# SCH_FB-Collar-Module_2024-04-16.net
KiCad netlist of a schematic drawn in EasyEDA
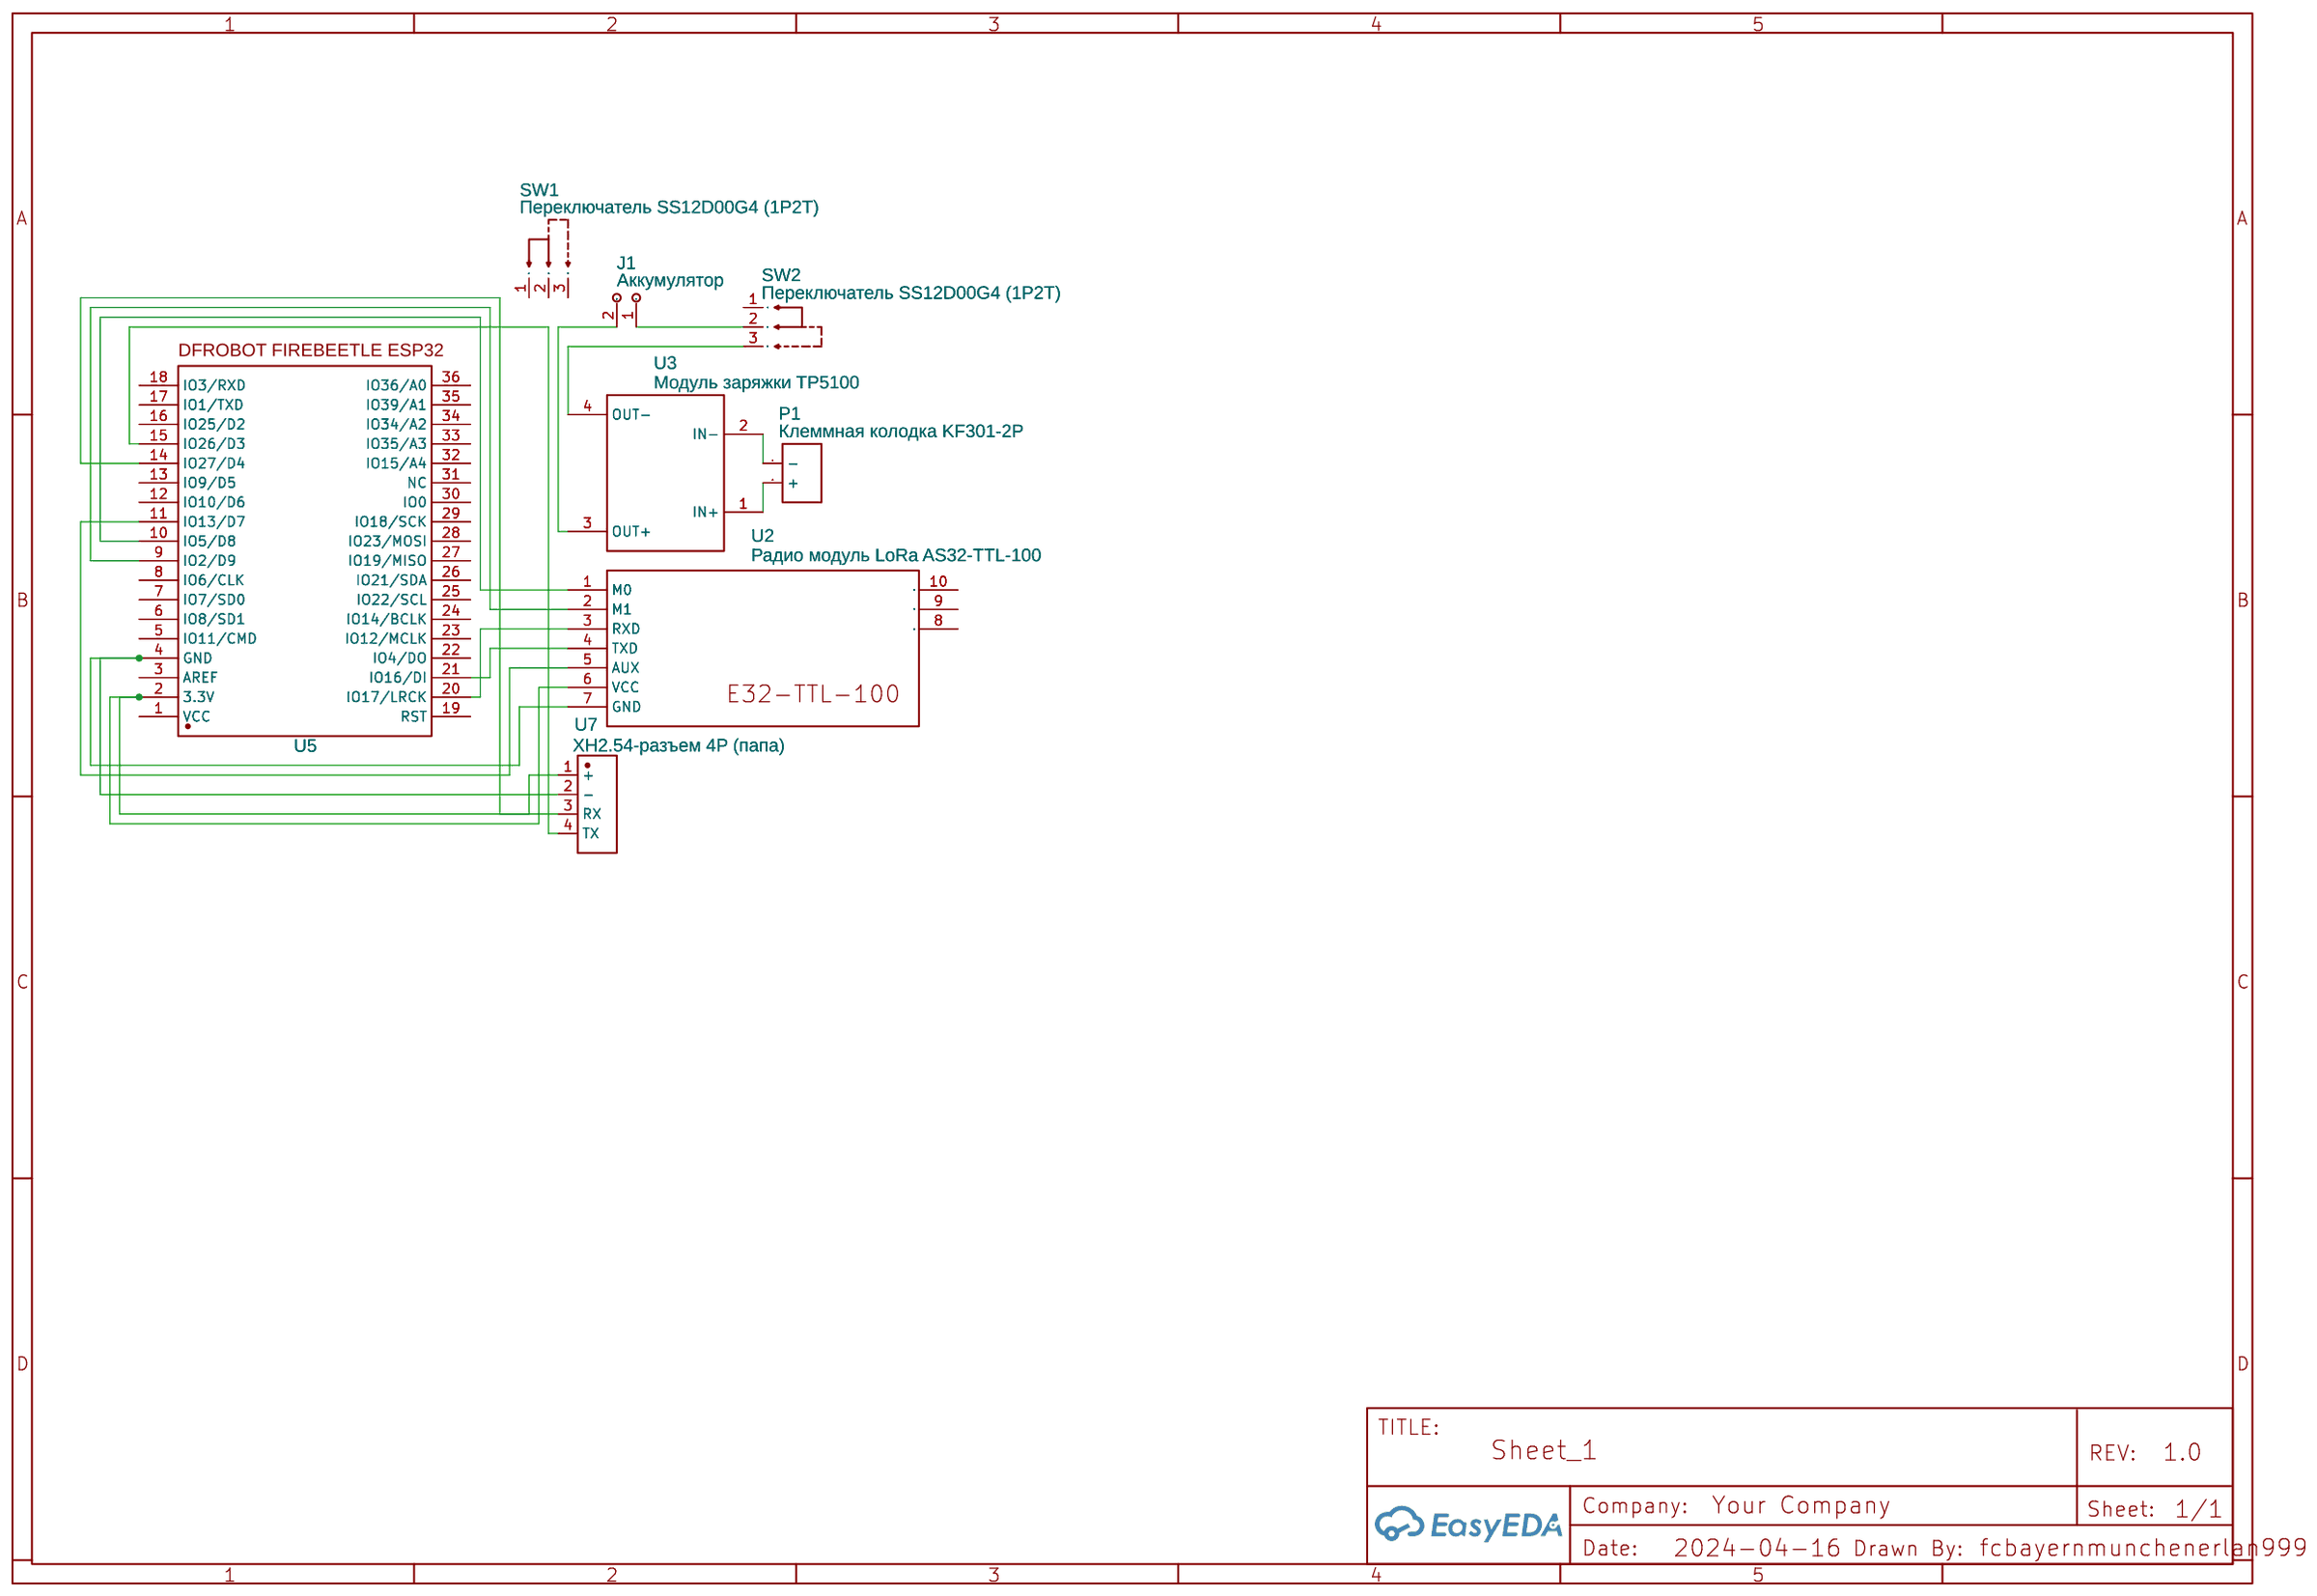
[diagram p0: schematic sheet]

(export (version "E")
  (design (tool "Eeschema 10.0.6"))
  (components
    (comp (ref "J1") (value "Аккумулятор") (libsource (lib "") (part "2xhole")))
    (comp (ref "P1") (value "Клеммная колодка KF301-2P") (libsource (lib "") (part "CONN-TH_2P-P5.00")))
    (comp (ref "SW1")
      (value "Переключатель SS12D00G4 (1P2T)")
      (fields (field (name "Manufacturer Part") "SS-12E17-G020") (field (name "Manufacturer") "G-Switch(品赞)"))
      (libsource (lib "") (part "SS-12E17-G020"))
    )
    (comp (ref "SW2")
      (value "Переключатель SS12D00G4 (1P2T)")
      (fields (field (name "Manufacturer Part") "SS-12E17-G020") (field (name "Manufacturer") "G-Switch(品赞)"))
      (libsource (lib "") (part "SS-12E17-G020_1"))
    )
    (comp (ref "U2")
      (value "Радио модуль LoRa AS32-TTL-100")
      (fields (field (name "Manufacturer Part") "E32-433T20DC") (field (name "Manufacturer") "EBYTE(亿佰特)"))
      (libsource (lib "") (part "E32-TTL-100"))
    )
    (comp (ref "U3") (value "Модуль заряжки TP5100") (libsource (lib "") (part "TP5100_MODULE_CHARGER")))
    (comp (ref "U5") (value "DFROBOT_FIREBEETLE") (libsource (lib "") (part "DFROBOT_FIREBEETLE")))
    (comp (ref "U7")
      (value "XH2.54-разъем 4P (папа)")
      (fields
        (field (name "Manufacturer Part") "ZX-XH2.54-4PWZ")
        (field (name "Manufacturer") "Megastar(兆星)")
      )
      (libsource (lib "") (part "ZX-XH2.54-4PWZ"))
    )
  )
  (nets
    (net (code "1") (name "Net-(J1-Pad1)") (class "Default")
      (node (ref "J1") (pin "1") (pinfunction "1_1") (pintype "unspecified"))
      (node (ref "SW2") (pin "2") (pinfunction "2_2") (pintype "unspecified"))
    )
    (net (code "2") (name "Net-(P1-+)") (class "Default")
      (node (ref "P1") (pin "2") (pinfunction "+_2") (pintype "unspecified"))
      (node (ref "U3") (pin "1") (pinfunction "IN+_1") (pintype "unspecified"))
    )
    (net (code "3") (name "Net-(P1--)") (class "Default")
      (node (ref "P1") (pin "1") (pinfunction "-_1") (pintype "unspecified"))
      (node (ref "U3") (pin "2") (pinfunction "IN-_2") (pintype "unspecified"))
    )
    (net (code "4") (name "Net-(U2-AUX)") (class "Default")
      (node (ref "U2") (pin "5") (pinfunction "AUX_5") (pintype "unspecified"))
      (node (ref "U5") (pin "11") (pinfunction "IO13/D7_11") (pintype "unspecified"))
    )
    (net (code "5") (name "Net-(U2-GND)") (class "Default")
      (node (ref "U2") (pin "7") (pinfunction "GND_7") (pintype "unspecified"))
      (node (ref "U5") (pin "4") (pinfunction "GND_4") (pintype "unspecified"))
      (node (ref "U7") (pin "2") (pinfunction "-_2") (pintype "unspecified"))
    )
    (net (code "6") (name "Net-(U2-M0)") (class "Default")
      (node (ref "U2") (pin "1") (pinfunction "M0_1") (pintype "unspecified"))
      (node (ref "U5") (pin "10") (pinfunction "IO5/D8_10") (pintype "unspecified"))
    )
    (net (code "7") (name "Net-(U2-M1)") (class "Default")
      (node (ref "U2") (pin "2") (pinfunction "M1_2") (pintype "unspecified"))
      (node (ref "U5") (pin "9") (pinfunction "IO2/D9_9") (pintype "unspecified"))
    )
    (net (code "8") (name "Net-(U2-RXD)") (class "Default")
      (node (ref "U2") (pin "3") (pinfunction "RXD_3") (pintype "unspecified"))
      (node (ref "U5") (pin "20") (pinfunction "IO17/LRCK_20") (pintype "unspecified"))
    )
    (net (code "9") (name "Net-(U2-TXD)") (class "Default")
      (node (ref "U2") (pin "4") (pinfunction "TXD_4") (pintype "unspecified"))
      (node (ref "U5") (pin "21") (pinfunction "IO16/DI_21") (pintype "unspecified"))
    )
    (net (code "10") (name "Net-(U2-VCC)") (class "Default")
      (node (ref "U2") (pin "6") (pinfunction "VCC_6") (pintype "passive"))
      (node (ref "U5") (pin "2") (pinfunction "3.3V_2") (pintype "unspecified"))
      (node (ref "U7") (pin "1") (pinfunction "+_1") (pintype "unspecified"))
    )
    (net (code "11") (name "Net-(U3-OUT+)") (class "Default")
      (node (ref "J1") (pin "2") (pinfunction "2_2") (pintype "unspecified"))
      (node (ref "U3") (pin "3") (pinfunction "OUT+_3") (pintype "unspecified"))
    )
    (net (code "12") (name "Net-(U3-OUT-)") (class "Default")
      (node (ref "SW2") (pin "3") (pinfunction "3_3") (pintype "unspecified"))
      (node (ref "U3") (pin "4") (pinfunction "OUT-_4") (pintype "unspecified"))
    )
    (net (code "13") (name "Net-(U5-IO26{slash}D3)") (class "Default")
      (node (ref "U5") (pin "15") (pinfunction "IO26/D3_15") (pintype "unspecified"))
      (node (ref "U7") (pin "4") (pinfunction "TX_4") (pintype "unspecified"))
    )
    (net (code "14") (name "Net-(U5-IO27{slash}D4)") (class "Default")
      (node (ref "U5") (pin "14") (pinfunction "IO27/D4_14") (pintype "unspecified"))
      (node (ref "U7") (pin "3") (pinfunction "RX_3") (pintype "unspecified"))
    )
    (net (code "15") (name "unconnected-(SW1-Pad1)") (class "Default")
      (node (ref "SW1") (pin "1") (pinfunction "1_1") (pintype "unspecified"))
    )
    (net (code "16") (name "unconnected-(SW1-Pad2)") (class "Default")
      (node (ref "SW1") (pin "2") (pinfunction "2_2") (pintype "unspecified"))
    )
    (net (code "17") (name "unconnected-(SW1-Pad3)") (class "Default")
      (node (ref "SW1") (pin "3") (pinfunction "3_3") (pintype "unspecified"))
    )
    (net (code "18") (name "unconnected-(SW2-Pad1)") (class "Default")
      (node (ref "SW2") (pin "1") (pinfunction "1_1") (pintype "unspecified"))
    )
    (net (code "19") (name "unconnected-(U2-Pad8)") (class "Default")
      (node (ref "U2") (pin "8") (pinfunction "8_8") (pintype "unspecified"))
    )
    (net (code "20") (name "unconnected-(U2-Pad9)") (class "Default")
      (node (ref "U2") (pin "9") (pinfunction "9_9") (pintype "unspecified"))
    )
    (net (code "21") (name "unconnected-(U2-Pad10)") (class "Default")
      (node (ref "U2") (pin "10") (pinfunction "10_10") (pintype "unspecified"))
    )
    (net (code "22") (name "unconnected-(U5-AREF-Pad3)") (class "Default")
      (node (ref "U5") (pin "3") (pinfunction "AREF_3") (pintype "unspecified"))
    )
    (net (code "23") (name "unconnected-(U5-IO0-Pad30)") (class "Default")
      (node (ref "U5") (pin "30") (pinfunction "IO0_30") (pintype "unspecified"))
    )
    (net (code "24") (name "unconnected-(U5-IO1{slash}TXD-Pad17)") (class "Default")
      (node (ref "U5") (pin "17") (pinfunction "IO1/TXD_17") (pintype "unspecified"))
    )
    (net (code "25") (name "unconnected-(U5-IO3{slash}RXD-Pad18)") (class "Default")
      (node (ref "U5") (pin "18") (pinfunction "IO3/RXD_18") (pintype "unspecified"))
    )
    (net (code "26") (name "unconnected-(U5-IO4{slash}DO-Pad22)") (class "Default")
      (node (ref "U5") (pin "22") (pinfunction "IO4/DO_22") (pintype "unspecified"))
    )
    (net (code "27") (name "unconnected-(U5-IO6{slash}CLK-Pad8)") (class "Default")
      (node (ref "U5") (pin "8") (pinfunction "IO6/CLK_8") (pintype "unspecified"))
    )
    (net (code "28") (name "unconnected-(U5-IO7{slash}SD0-Pad7)") (class "Default")
      (node (ref "U5") (pin "7") (pinfunction "IO7/SD0_7") (pintype "unspecified"))
    )
    (net (code "29") (name "unconnected-(U5-IO8{slash}SD1-Pad6)") (class "Default")
      (node (ref "U5") (pin "6") (pinfunction "IO8/SD1_6") (pintype "unspecified"))
    )
    (net (code "30") (name "unconnected-(U5-IO9{slash}D5-Pad13)") (class "Default")
      (node (ref "U5") (pin "13") (pinfunction "IO9/D5_13") (pintype "unspecified"))
    )
    (net (code "31") (name "unconnected-(U5-IO10{slash}D6-Pad12)") (class "Default")
      (node (ref "U5") (pin "12") (pinfunction "IO10/D6_12") (pintype "unspecified"))
    )
    (net (code "32") (name "unconnected-(U5-IO11{slash}CMD-Pad5)") (class "Default")
      (node (ref "U5") (pin "5") (pinfunction "IO11/CMD_5") (pintype "unspecified"))
    )
    (net (code "33") (name "unconnected-(U5-IO12{slash}MCLK-Pad23)") (class "Default")
      (node (ref "U5") (pin "23") (pinfunction "IO12/MCLK_23") (pintype "unspecified"))
    )
    (net (code "34") (name "unconnected-(U5-IO14{slash}BCLK-Pad24)") (class "Default")
      (node (ref "U5") (pin "24") (pinfunction "IO14/BCLK_24") (pintype "unspecified"))
    )
    (net (code "35") (name "unconnected-(U5-IO15{slash}A4-Pad32)") (class "Default")
      (node (ref "U5") (pin "32") (pinfunction "IO15/A4_32") (pintype "unspecified"))
    )
    (net (code "36") (name "unconnected-(U5-IO18{slash}SCK-Pad29)") (class "Default")
      (node (ref "U5") (pin "29") (pinfunction "IO18/SCK_29") (pintype "unspecified"))
    )
    (net (code "37") (name "unconnected-(U5-IO19{slash}MISO-Pad27)") (class "Default")
      (node (ref "U5") (pin "27") (pinfunction "IO19/MISO_27") (pintype "unspecified"))
    )
    (net (code "38") (name "unconnected-(U5-IO21{slash}SDA-Pad26)") (class "Default")
      (node (ref "U5") (pin "26") (pinfunction "IO21/SDA_26") (pintype "unspecified"))
    )
    (net (code "39") (name "unconnected-(U5-IO22{slash}SCL-Pad25)") (class "Default")
      (node (ref "U5") (pin "25") (pinfunction "IO22/SCL_25") (pintype "unspecified"))
    )
    (net (code "40") (name "unconnected-(U5-IO23{slash}MOSI-Pad28)") (class "Default")
      (node (ref "U5") (pin "28") (pinfunction "IO23/MOSI_28") (pintype "unspecified"))
    )
    (net (code "41") (name "unconnected-(U5-IO25{slash}D2-Pad16)") (class "Default")
      (node (ref "U5") (pin "16") (pinfunction "IO25/D2_16") (pintype "unspecified"))
    )
    (net (code "42") (name "unconnected-(U5-IO34{slash}A2-Pad34)") (class "Default")
      (node (ref "U5") (pin "34") (pinfunction "IO34/A2_34") (pintype "unspecified"))
    )
    (net (code "43") (name "unconnected-(U5-IO35{slash}A3-Pad33)") (class "Default")
      (node (ref "U5") (pin "33") (pinfunction "IO35/A3_33") (pintype "unspecified"))
    )
    (net (code "44") (name "unconnected-(U5-IO36{slash}A0-Pad36)") (class "Default")
      (node (ref "U5") (pin "36") (pinfunction "IO36/A0_36") (pintype "unspecified"))
    )
    (net (code "45") (name "unconnected-(U5-IO39{slash}A1-Pad35)") (class "Default")
      (node (ref "U5") (pin "35") (pinfunction "IO39/A1_35") (pintype "unspecified"))
    )
    (net (code "46") (name "unconnected-(U5-NC-Pad31)") (class "Default")
      (node (ref "U5") (pin "31") (pinfunction "NC_31") (pintype "unspecified"))
    )
    (net (code "47") (name "unconnected-(U5-RST-Pad19)") (class "Default")
      (node (ref "U5") (pin "19") (pinfunction "RST_19") (pintype "unspecified"))
    )
    (net (code "48") (name "unconnected-(U5-VCC-Pad1)") (class "Default")
      (node (ref "U5") (pin "1") (pinfunction "VCC_1") (pintype "unspecified"))
    )
  )
)
